# Adafruit_NeoPixel_Ring_24_B.net
KiCad netlist of a schematic drawn in EAGLE
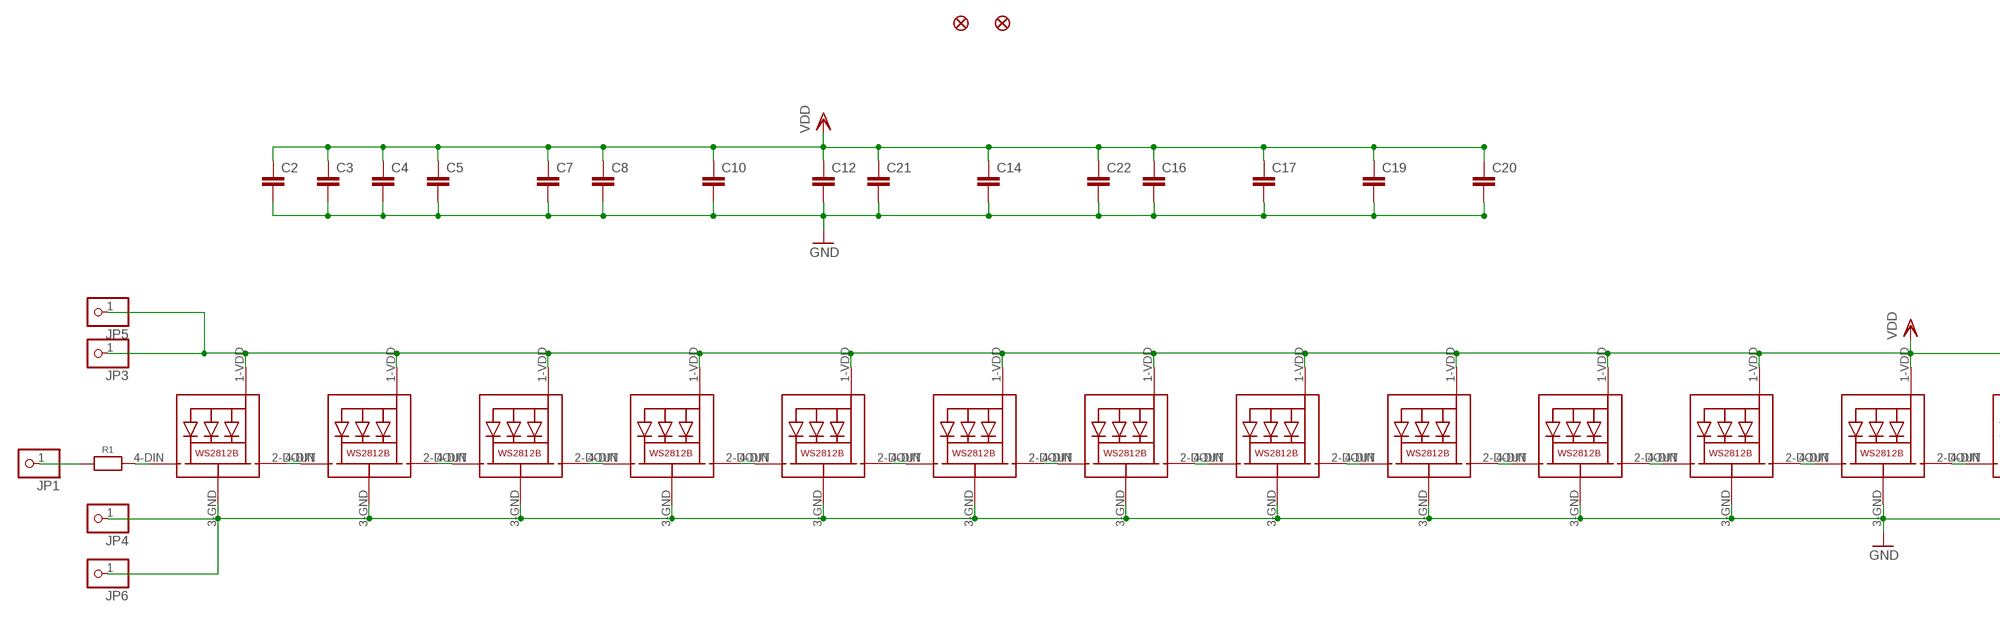
[diagram p0: schematic, sheet 1, part 1 of 2]
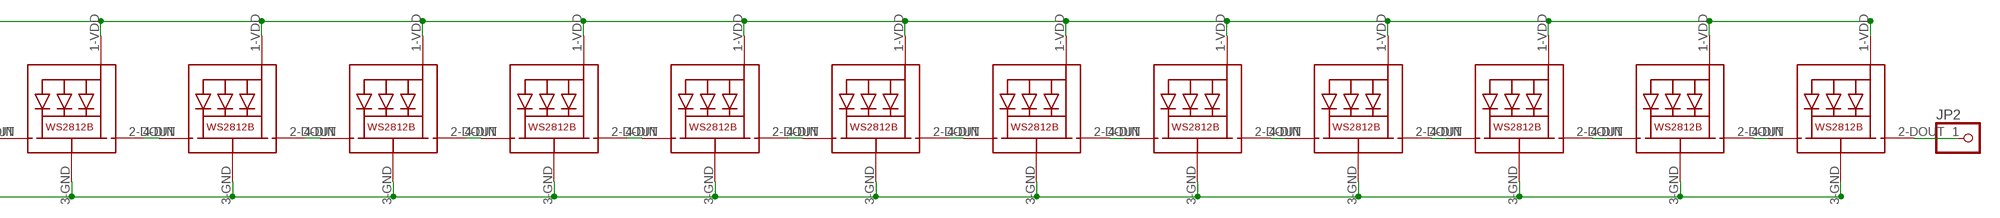
[diagram p1: schematic, sheet 1, part 2 of 2]

(export (version "E")
  (design (tool "Eeschema 10.0.6"))
  (components
    (comp (ref "C2")
      (value "C-EUC0603")
      (footprint "eagle-import:C0603")
      (libsource (lib "eagle-import") (part "C-EUC0603"))
    )
    (comp (ref "C3")
      (value "C-EUC0603")
      (footprint "eagle-import:C0603")
      (libsource (lib "eagle-import") (part "C-EUC0603"))
    )
    (comp (ref "C4")
      (value "C-EUC0603")
      (footprint "eagle-import:C0603")
      (libsource (lib "eagle-import") (part "C-EUC0603"))
    )
    (comp (ref "C5")
      (value "C-EUC0603")
      (footprint "eagle-import:C0603")
      (libsource (lib "eagle-import") (part "C-EUC0603"))
    )
    (comp (ref "C7")
      (value "C-EUC0603")
      (footprint "eagle-import:C0603")
      (libsource (lib "eagle-import") (part "C-EUC0603"))
    )
    (comp (ref "C8")
      (value "C-EUC0603")
      (footprint "eagle-import:C0603")
      (libsource (lib "eagle-import") (part "C-EUC0603"))
    )
    (comp (ref "C10")
      (value "C-EUC0603")
      (footprint "eagle-import:C0603")
      (libsource (lib "eagle-import") (part "C-EUC0603"))
    )
    (comp (ref "C12")
      (value "C-EUC0603")
      (footprint "eagle-import:C0603")
      (libsource (lib "eagle-import") (part "C-EUC0603"))
    )
    (comp (ref "C14")
      (value "C-EUC0603")
      (footprint "eagle-import:C0603")
      (libsource (lib "eagle-import") (part "C-EUC0603"))
    )
    (comp (ref "C16")
      (value "C-EUC0603")
      (footprint "eagle-import:C0603")
      (libsource (lib "eagle-import") (part "C-EUC0603"))
    )
    (comp (ref "C17")
      (value "C-EUC0603")
      (footprint "eagle-import:C0603")
      (libsource (lib "eagle-import") (part "C-EUC0603"))
    )
    (comp (ref "C19")
      (value "C-EUC0603")
      (footprint "eagle-import:C0603")
      (libsource (lib "eagle-import") (part "C-EUC0603"))
    )
    (comp (ref "C20")
      (value "C-EUC0603")
      (footprint "eagle-import:C0603")
      (libsource (lib "eagle-import") (part "C-EUC0603"))
    )
    (comp (ref "C21")
      (value "C-EUC0603")
      (footprint "eagle-import:C0603")
      (libsource (lib "eagle-import") (part "C-EUC0603"))
    )
    (comp (ref "C22")
      (value "C-EUC0603")
      (footprint "eagle-import:C0603")
      (libsource (lib "eagle-import") (part "C-EUC0603"))
    )
    (comp (ref "FID1")
      (value "FIDUCIAL\"\"")
      (footprint "eagle-import:FIDUCIAL_1MM")
      (libsource (lib "eagle-import") (part "FIDUCIAL{dblquote}{dblquote}"))
    )
    (comp (ref "FID2")
      (value "FIDUCIAL\"\"")
      (footprint "eagle-import:FIDUCIAL_1MM")
      (libsource (lib "eagle-import") (part "FIDUCIAL{dblquote}{dblquote}"))
    )
    (comp (ref "JP1")
      (value "PINHD-1X1CB")
      (footprint "eagle-import:1X01-CLEANBIG")
      (libsource (lib "eagle-import") (part "PINHD-1X1CB"))
    )
    (comp (ref "JP2")
      (value "PINHD-1X1CB")
      (footprint "eagle-import:1X01-CLEANBIG")
      (libsource (lib "eagle-import") (part "PINHD-1X1CB"))
    )
    (comp (ref "JP3")
      (value "PINHD-1X1CB")
      (footprint "eagle-import:1X01-CLEANBIG")
      (libsource (lib "eagle-import") (part "PINHD-1X1CB"))
    )
    (comp (ref "JP4")
      (value "PINHD-1X1CB")
      (footprint "eagle-import:1X01-CLEANBIG")
      (libsource (lib "eagle-import") (part "PINHD-1X1CB"))
    )
    (comp (ref "JP5")
      (value "PINHD-1X1CB")
      (footprint "eagle-import:1X01-CLEANBIG")
      (libsource (lib "eagle-import") (part "PINHD-1X1CB"))
    )
    (comp (ref "JP6")
      (value "PINHD-1X1CB")
      (footprint "eagle-import:1X01-CLEANBIG")
      (libsource (lib "eagle-import") (part "PINHD-1X1CB"))
    )
    (comp (ref "LED1")
      (value "WS2812B5050")
      (footprint "eagle-import:WS2812B")
      (libsource (lib "eagle-import") (part "WS2812B5050"))
    )
    (comp (ref "LED2")
      (value "WS2812B5050")
      (footprint "eagle-import:WS2812B")
      (libsource (lib "eagle-import") (part "WS2812B5050"))
    )
    (comp (ref "LED3")
      (value "WS2812B5050")
      (footprint "eagle-import:WS2812B")
      (libsource (lib "eagle-import") (part "WS2812B5050"))
    )
    (comp (ref "LED4")
      (value "WS2812B5050")
      (footprint "eagle-import:WS2812B")
      (libsource (lib "eagle-import") (part "WS2812B5050"))
    )
    (comp (ref "LED5")
      (value "WS2812B5050")
      (footprint "eagle-import:WS2812B")
      (libsource (lib "eagle-import") (part "WS2812B5050"))
    )
    (comp (ref "LED6")
      (value "WS2812B5050")
      (footprint "eagle-import:WS2812B")
      (libsource (lib "eagle-import") (part "WS2812B5050"))
    )
    (comp (ref "LED7")
      (value "WS2812B5050")
      (footprint "eagle-import:WS2812B")
      (libsource (lib "eagle-import") (part "WS2812B5050"))
    )
    (comp (ref "LED8")
      (value "WS2812B5050")
      (footprint "eagle-import:WS2812B")
      (libsource (lib "eagle-import") (part "WS2812B5050"))
    )
    (comp (ref "LED9")
      (value "WS2812B5050")
      (footprint "eagle-import:WS2812B")
      (libsource (lib "eagle-import") (part "WS2812B5050"))
    )
    (comp (ref "LED10")
      (value "WS2812B5050")
      (footprint "eagle-import:WS2812B")
      (libsource (lib "eagle-import") (part "WS2812B5050"))
    )
    (comp (ref "LED11")
      (value "WS2812B5050")
      (footprint "eagle-import:WS2812B")
      (libsource (lib "eagle-import") (part "WS2812B5050"))
    )
    (comp (ref "LED12")
      (value "WS2812B5050")
      (footprint "eagle-import:WS2812B")
      (libsource (lib "eagle-import") (part "WS2812B5050"))
    )
    (comp (ref "LED13")
      (value "WS2812B5050")
      (footprint "eagle-import:WS2812B")
      (libsource (lib "eagle-import") (part "WS2812B5050"))
    )
    (comp (ref "LED14")
      (value "WS2812B5050")
      (footprint "eagle-import:WS2812B")
      (libsource (lib "eagle-import") (part "WS2812B5050"))
    )
    (comp (ref "LED15")
      (value "WS2812B5050")
      (footprint "eagle-import:WS2812B")
      (libsource (lib "eagle-import") (part "WS2812B5050"))
    )
    (comp (ref "LED16")
      (value "WS2812B5050")
      (footprint "eagle-import:WS2812B")
      (libsource (lib "eagle-import") (part "WS2812B5050"))
    )
    (comp (ref "LED17")
      (value "WS2812B5050")
      (footprint "eagle-import:WS2812B")
      (libsource (lib "eagle-import") (part "WS2812B5050"))
    )
    (comp (ref "LED18")
      (value "WS2812B5050")
      (footprint "eagle-import:WS2812B")
      (libsource (lib "eagle-import") (part "WS2812B5050"))
    )
    (comp (ref "LED19")
      (value "WS2812B5050")
      (footprint "eagle-import:WS2812B")
      (libsource (lib "eagle-import") (part "WS2812B5050"))
    )
    (comp (ref "LED20")
      (value "WS2812B5050")
      (footprint "eagle-import:WS2812B")
      (libsource (lib "eagle-import") (part "WS2812B5050"))
    )
    (comp (ref "LED21")
      (value "WS2812B5050")
      (footprint "eagle-import:WS2812B")
      (libsource (lib "eagle-import") (part "WS2812B5050"))
    )
    (comp (ref "LED22")
      (value "WS2812B5050")
      (footprint "eagle-import:WS2812B")
      (libsource (lib "eagle-import") (part "WS2812B5050"))
    )
    (comp (ref "LED23")
      (value "WS2812B5050")
      (footprint "eagle-import:WS2812B")
      (libsource (lib "eagle-import") (part "WS2812B5050"))
    )
    (comp (ref "LED24")
      (value "WS2812B5050")
      (footprint "eagle-import:WS2812B")
      (libsource (lib "eagle-import") (part "WS2812B5050"))
    )
    (comp (ref "R1")
      (value "RESISTOR_0603_NOOUT")
      (footprint "eagle-import:0603-NO")
      (libsource (lib "eagle-import") (part "RESISTOR_0603_NOOUT"))
    )
  )
  (nets
    (net (code "1") (name "GND") (class "Default")
      (node (ref "C10") (pin "2") (pinfunction "2_2") (pintype "passive"))
      (node (ref "C12") (pin "2") (pinfunction "2_2") (pintype "passive"))
      (node (ref "C14") (pin "2") (pinfunction "2_2") (pintype "passive"))
      (node (ref "C16") (pin "2") (pinfunction "2_2") (pintype "passive"))
      (node (ref "C17") (pin "2") (pinfunction "2_2") (pintype "passive"))
      (node (ref "C19") (pin "2") (pinfunction "2_2") (pintype "passive"))
      (node (ref "C2") (pin "2") (pinfunction "2_2") (pintype "passive"))
      (node (ref "C20") (pin "2") (pinfunction "2_2") (pintype "passive"))
      (node (ref "C21") (pin "2") (pinfunction "2_2") (pintype "passive"))
      (node (ref "C22") (pin "2") (pinfunction "2_2") (pintype "passive"))
      (node (ref "C3") (pin "2") (pinfunction "2_2") (pintype "passive"))
      (node (ref "C4") (pin "2") (pinfunction "2_2") (pintype "passive"))
      (node (ref "C5") (pin "2") (pinfunction "2_2") (pintype "passive"))
      (node (ref "C7") (pin "2") (pinfunction "2_2") (pintype "passive"))
      (node (ref "C8") (pin "2") (pinfunction "2_2") (pintype "passive"))
      (node (ref "JP4") (pin "1") (pinfunction "1_1") (pintype "passive"))
      (node (ref "JP6") (pin "1") (pinfunction "1_1") (pintype "passive"))
      (node (ref "LED1") (pin "3-GND") (pinfunction "GND_3-GND") (pintype "power_in"))
      (node (ref "LED10") (pin "3-GND") (pinfunction "GND_3-GND") (pintype "power_in"))
      (node (ref "LED11") (pin "3-GND") (pinfunction "GND_3-GND") (pintype "power_in"))
      (node (ref "LED12") (pin "3-GND") (pinfunction "GND_3-GND") (pintype "power_in"))
      (node (ref "LED13") (pin "3-GND") (pinfunction "GND_3-GND") (pintype "power_in"))
      (node (ref "LED14") (pin "3-GND") (pinfunction "GND_3-GND") (pintype "power_in"))
      (node (ref "LED15") (pin "3-GND") (pinfunction "GND_3-GND") (pintype "power_in"))
      (node (ref "LED16") (pin "3-GND") (pinfunction "GND_3-GND") (pintype "power_in"))
      (node (ref "LED17") (pin "3-GND") (pinfunction "GND_3-GND") (pintype "power_in"))
      (node (ref "LED18") (pin "3-GND") (pinfunction "GND_3-GND") (pintype "power_in"))
      (node (ref "LED19") (pin "3-GND") (pinfunction "GND_3-GND") (pintype "power_in"))
      (node (ref "LED2") (pin "3-GND") (pinfunction "GND_3-GND") (pintype "power_in"))
      (node (ref "LED20") (pin "3-GND") (pinfunction "GND_3-GND") (pintype "power_in"))
      (node (ref "LED21") (pin "3-GND") (pinfunction "GND_3-GND") (pintype "power_in"))
      (node (ref "LED22") (pin "3-GND") (pinfunction "GND_3-GND") (pintype "power_in"))
      (node (ref "LED23") (pin "3-GND") (pinfunction "GND_3-GND") (pintype "power_in"))
      (node (ref "LED24") (pin "3-GND") (pinfunction "GND_3-GND") (pintype "power_in"))
      (node (ref "LED3") (pin "3-GND") (pinfunction "GND_3-GND") (pintype "power_in"))
      (node (ref "LED4") (pin "3-GND") (pinfunction "GND_3-GND") (pintype "power_in"))
      (node (ref "LED5") (pin "3-GND") (pinfunction "GND_3-GND") (pintype "power_in"))
      (node (ref "LED6") (pin "3-GND") (pinfunction "GND_3-GND") (pintype "power_in"))
      (node (ref "LED7") (pin "3-GND") (pinfunction "GND_3-GND") (pintype "power_in"))
      (node (ref "LED8") (pin "3-GND") (pinfunction "GND_3-GND") (pintype "power_in"))
      (node (ref "LED9") (pin "3-GND") (pinfunction "GND_3-GND") (pintype "power_in"))
    )
    (net (code "2") (name "Net-(JP1-Pad1)") (class "Default")
      (node (ref "JP1") (pin "1") (pinfunction "1_1") (pintype "passive"))
      (node (ref "R1") (pin "1") (pinfunction "1_1") (pintype "passive"))
    )
    (net (code "3") (name "Net-(LED1-DI)") (class "Default")
      (node (ref "LED1") (pin "4-DIN") (pinfunction "DI_4-DIN") (pintype "input"))
      (node (ref "R1") (pin "2") (pinfunction "2_2") (pintype "passive"))
    )
    (net (code "4") (name "Net-(LED1-DO)") (class "Default")
      (node (ref "LED1") (pin "2-DOUT") (pinfunction "DO_2-DOUT") (pintype "output"))
      (node (ref "LED2") (pin "4-DIN") (pinfunction "DI_4-DIN") (pintype "input"))
    )
    (net (code "5") (name "Net-(LED2-DO)") (class "Default")
      (node (ref "LED2") (pin "2-DOUT") (pinfunction "DO_2-DOUT") (pintype "output"))
      (node (ref "LED3") (pin "4-DIN") (pinfunction "DI_4-DIN") (pintype "input"))
    )
    (net (code "6") (name "Net-(LED3-DO)") (class "Default")
      (node (ref "LED3") (pin "2-DOUT") (pinfunction "DO_2-DOUT") (pintype "output"))
      (node (ref "LED4") (pin "4-DIN") (pinfunction "DI_4-DIN") (pintype "input"))
    )
    (net (code "7") (name "Net-(LED4-DO)") (class "Default")
      (node (ref "LED4") (pin "2-DOUT") (pinfunction "DO_2-DOUT") (pintype "output"))
      (node (ref "LED5") (pin "4-DIN") (pinfunction "DI_4-DIN") (pintype "input"))
    )
    (net (code "8") (name "Net-(LED5-DO)") (class "Default")
      (node (ref "LED5") (pin "2-DOUT") (pinfunction "DO_2-DOUT") (pintype "output"))
      (node (ref "LED6") (pin "4-DIN") (pinfunction "DI_4-DIN") (pintype "input"))
    )
    (net (code "9") (name "Net-(LED6-DO)") (class "Default")
      (node (ref "LED6") (pin "2-DOUT") (pinfunction "DO_2-DOUT") (pintype "output"))
      (node (ref "LED7") (pin "4-DIN") (pinfunction "DI_4-DIN") (pintype "input"))
    )
    (net (code "10") (name "Net-(LED7-DO)") (class "Default")
      (node (ref "LED7") (pin "2-DOUT") (pinfunction "DO_2-DOUT") (pintype "output"))
      (node (ref "LED8") (pin "4-DIN") (pinfunction "DI_4-DIN") (pintype "input"))
    )
    (net (code "11") (name "Net-(LED8-DO)") (class "Default")
      (node (ref "LED8") (pin "2-DOUT") (pinfunction "DO_2-DOUT") (pintype "output"))
      (node (ref "LED9") (pin "4-DIN") (pinfunction "DI_4-DIN") (pintype "input"))
    )
    (net (code "12") (name "Net-(LED10-DI)") (class "Default")
      (node (ref "LED10") (pin "4-DIN") (pinfunction "DI_4-DIN") (pintype "input"))
      (node (ref "LED9") (pin "2-DOUT") (pinfunction "DO_2-DOUT") (pintype "output"))
    )
    (net (code "13") (name "Net-(LED10-DO)") (class "Default")
      (node (ref "LED10") (pin "2-DOUT") (pinfunction "DO_2-DOUT") (pintype "output"))
      (node (ref "LED11") (pin "4-DIN") (pinfunction "DI_4-DIN") (pintype "input"))
    )
    (net (code "14") (name "Net-(LED11-DO)") (class "Default")
      (node (ref "LED11") (pin "2-DOUT") (pinfunction "DO_2-DOUT") (pintype "output"))
      (node (ref "LED12") (pin "4-DIN") (pinfunction "DI_4-DIN") (pintype "input"))
    )
    (net (code "15") (name "Net-(LED12-DO)") (class "Default")
      (node (ref "LED12") (pin "2-DOUT") (pinfunction "DO_2-DOUT") (pintype "output"))
      (node (ref "LED13") (pin "4-DIN") (pinfunction "DI_4-DIN") (pintype "input"))
    )
    (net (code "16") (name "Net-(LED13-DO)") (class "Default")
      (node (ref "LED13") (pin "2-DOUT") (pinfunction "DO_2-DOUT") (pintype "output"))
      (node (ref "LED14") (pin "4-DIN") (pinfunction "DI_4-DIN") (pintype "input"))
    )
    (net (code "17") (name "Net-(LED14-DO)") (class "Default")
      (node (ref "LED14") (pin "2-DOUT") (pinfunction "DO_2-DOUT") (pintype "output"))
      (node (ref "LED15") (pin "4-DIN") (pinfunction "DI_4-DIN") (pintype "input"))
    )
    (net (code "18") (name "Net-(LED15-DO)") (class "Default")
      (node (ref "LED15") (pin "2-DOUT") (pinfunction "DO_2-DOUT") (pintype "output"))
      (node (ref "LED16") (pin "4-DIN") (pinfunction "DI_4-DIN") (pintype "input"))
    )
    (net (code "19") (name "Net-(LED16-DO)") (class "Default")
      (node (ref "LED16") (pin "2-DOUT") (pinfunction "DO_2-DOUT") (pintype "output"))
      (node (ref "LED17") (pin "4-DIN") (pinfunction "DI_4-DIN") (pintype "input"))
    )
    (net (code "20") (name "Net-(LED17-DO)") (class "Default")
      (node (ref "LED17") (pin "2-DOUT") (pinfunction "DO_2-DOUT") (pintype "output"))
      (node (ref "LED18") (pin "4-DIN") (pinfunction "DI_4-DIN") (pintype "input"))
    )
    (net (code "21") (name "Net-(LED18-DO)") (class "Default")
      (node (ref "LED18") (pin "2-DOUT") (pinfunction "DO_2-DOUT") (pintype "output"))
      (node (ref "LED19") (pin "4-DIN") (pinfunction "DI_4-DIN") (pintype "input"))
    )
    (net (code "22") (name "Net-(LED19-DO)") (class "Default")
      (node (ref "LED19") (pin "2-DOUT") (pinfunction "DO_2-DOUT") (pintype "output"))
      (node (ref "LED20") (pin "4-DIN") (pinfunction "DI_4-DIN") (pintype "input"))
    )
    (net (code "23") (name "Net-(LED20-DO)") (class "Default")
      (node (ref "LED20") (pin "2-DOUT") (pinfunction "DO_2-DOUT") (pintype "output"))
      (node (ref "LED21") (pin "4-DIN") (pinfunction "DI_4-DIN") (pintype "input"))
    )
    (net (code "24") (name "Net-(LED21-DO)") (class "Default")
      (node (ref "LED21") (pin "2-DOUT") (pinfunction "DO_2-DOUT") (pintype "output"))
      (node (ref "LED22") (pin "4-DIN") (pinfunction "DI_4-DIN") (pintype "input"))
    )
    (net (code "25") (name "Net-(LED22-DO)") (class "Default")
      (node (ref "LED22") (pin "2-DOUT") (pinfunction "DO_2-DOUT") (pintype "output"))
      (node (ref "LED23") (pin "4-DIN") (pinfunction "DI_4-DIN") (pintype "input"))
    )
    (net (code "26") (name "Net-(LED23-DO)") (class "Default")
      (node (ref "LED23") (pin "2-DOUT") (pinfunction "DO_2-DOUT") (pintype "output"))
      (node (ref "LED24") (pin "4-DIN") (pinfunction "DI_4-DIN") (pintype "input"))
    )
    (net (code "27") (name "Net-(LED24-DO)") (class "Default")
      (node (ref "JP2") (pin "1") (pinfunction "1_1") (pintype "passive"))
      (node (ref "LED24") (pin "2-DOUT") (pinfunction "DO_2-DOUT") (pintype "output"))
    )
    (net (code "28") (name "VDD") (class "Default")
      (node (ref "C10") (pin "1") (pinfunction "1_1") (pintype "passive"))
      (node (ref "C12") (pin "1") (pinfunction "1_1") (pintype "passive"))
      (node (ref "C14") (pin "1") (pinfunction "1_1") (pintype "passive"))
      (node (ref "C16") (pin "1") (pinfunction "1_1") (pintype "passive"))
      (node (ref "C17") (pin "1") (pinfunction "1_1") (pintype "passive"))
      (node (ref "C19") (pin "1") (pinfunction "1_1") (pintype "passive"))
      (node (ref "C2") (pin "1") (pinfunction "1_1") (pintype "passive"))
      (node (ref "C20") (pin "1") (pinfunction "1_1") (pintype "passive"))
      (node (ref "C21") (pin "1") (pinfunction "1_1") (pintype "passive"))
      (node (ref "C22") (pin "1") (pinfunction "1_1") (pintype "passive"))
      (node (ref "C3") (pin "1") (pinfunction "1_1") (pintype "passive"))
      (node (ref "C4") (pin "1") (pinfunction "1_1") (pintype "passive"))
      (node (ref "C5") (pin "1") (pinfunction "1_1") (pintype "passive"))
      (node (ref "C7") (pin "1") (pinfunction "1_1") (pintype "passive"))
      (node (ref "C8") (pin "1") (pinfunction "1_1") (pintype "passive"))
      (node (ref "JP3") (pin "1") (pinfunction "1_1") (pintype "passive"))
      (node (ref "JP5") (pin "1") (pinfunction "1_1") (pintype "passive"))
      (node (ref "LED1") (pin "1-VDD") (pinfunction "VDD_1-VDD") (pintype "power_in"))
      (node (ref "LED10") (pin "1-VDD") (pinfunction "VDD_1-VDD") (pintype "power_in"))
      (node (ref "LED11") (pin "1-VDD") (pinfunction "VDD_1-VDD") (pintype "power_in"))
      (node (ref "LED12") (pin "1-VDD") (pinfunction "VDD_1-VDD") (pintype "power_in"))
      (node (ref "LED13") (pin "1-VDD") (pinfunction "VDD_1-VDD") (pintype "power_in"))
      (node (ref "LED14") (pin "1-VDD") (pinfunction "VDD_1-VDD") (pintype "power_in"))
      (node (ref "LED15") (pin "1-VDD") (pinfunction "VDD_1-VDD") (pintype "power_in"))
      (node (ref "LED16") (pin "1-VDD") (pinfunction "VDD_1-VDD") (pintype "power_in"))
      (node (ref "LED17") (pin "1-VDD") (pinfunction "VDD_1-VDD") (pintype "power_in"))
      (node (ref "LED18") (pin "1-VDD") (pinfunction "VDD_1-VDD") (pintype "power_in"))
      (node (ref "LED19") (pin "1-VDD") (pinfunction "VDD_1-VDD") (pintype "power_in"))
      (node (ref "LED2") (pin "1-VDD") (pinfunction "VDD_1-VDD") (pintype "power_in"))
      (node (ref "LED20") (pin "1-VDD") (pinfunction "VDD_1-VDD") (pintype "power_in"))
      (node (ref "LED21") (pin "1-VDD") (pinfunction "VDD_1-VDD") (pintype "power_in"))
      (node (ref "LED22") (pin "1-VDD") (pinfunction "VDD_1-VDD") (pintype "power_in"))
      (node (ref "LED23") (pin "1-VDD") (pinfunction "VDD_1-VDD") (pintype "power_in"))
      (node (ref "LED24") (pin "1-VDD") (pinfunction "VDD_1-VDD") (pintype "power_in"))
      (node (ref "LED3") (pin "1-VDD") (pinfunction "VDD_1-VDD") (pintype "power_in"))
      (node (ref "LED4") (pin "1-VDD") (pinfunction "VDD_1-VDD") (pintype "power_in"))
      (node (ref "LED5") (pin "1-VDD") (pinfunction "VDD_1-VDD") (pintype "power_in"))
      (node (ref "LED6") (pin "1-VDD") (pinfunction "VDD_1-VDD") (pintype "power_in"))
      (node (ref "LED7") (pin "1-VDD") (pinfunction "VDD_1-VDD") (pintype "power_in"))
      (node (ref "LED8") (pin "1-VDD") (pinfunction "VDD_1-VDD") (pintype "power_in"))
      (node (ref "LED9") (pin "1-VDD") (pinfunction "VDD_1-VDD") (pintype "power_in"))
    )
  )
)
